# Kitchenkopf-v1.net
KiCad netlist of a schematic drawn in EAGLE
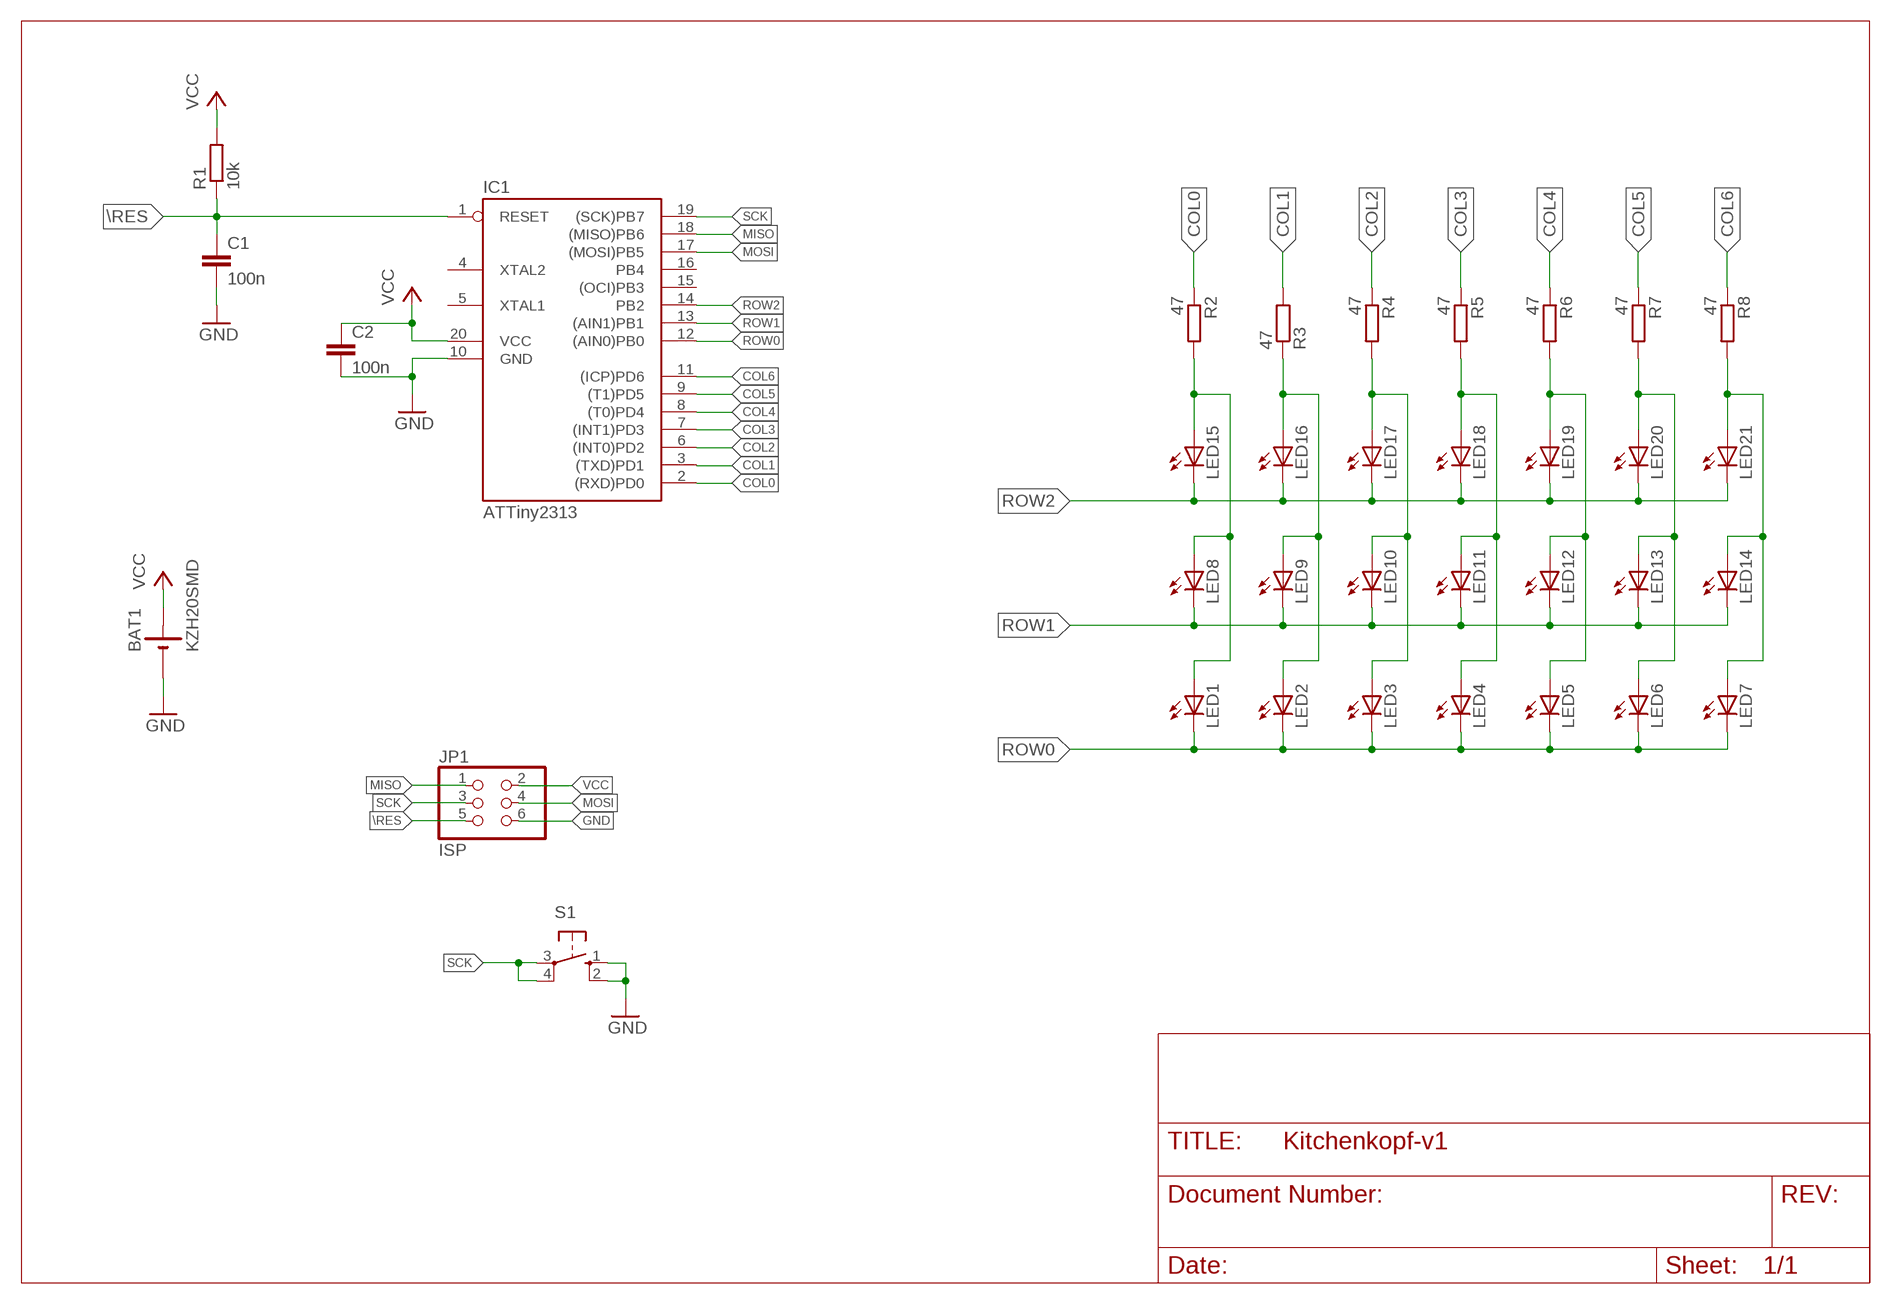
[diagram p0: schematic, sheet 1]

(export (version "E")
  (design (tool "Eeschema 10.0.6"))
  (components
    (comp (ref "BAT1")
      (value "KZH20SMD")
      (footprint "eagle-import:KZH20SMD")
      (libsource (lib "eagle-import") (part "KZH20SMD"))
    )
    (comp (ref "C1")
      (value "100n")
      (footprint "eagle-import:C0805")
      (libsource (lib "eagle-import") (part "C-EUC0805"))
    )
    (comp (ref "C2")
      (value "100n")
      (footprint "eagle-import:C0805")
      (libsource (lib "eagle-import") (part "C-EUC0805"))
    )
    (comp (ref "IC1")
      (value "ATTiny2313")
      (footprint "eagle-import:SO20L")
      (libsource (lib "eagle-import") (part "AT90S2313S"))
    )
    (comp (ref "JP1")
      (value "ISP")
      (footprint "eagle-import:2X03")
      (libsource (lib "eagle-import") (part "PINHD-2X3"))
    )
    (comp (ref "LED1")
      (value "LEDCHIP-LED0805")
      (footprint "eagle-import:CHIP-LED0805")
      (libsource (lib "eagle-import") (part "LEDCHIP-LED0805"))
    )
    (comp (ref "LED2")
      (value "LEDCHIP-LED0805")
      (footprint "eagle-import:CHIP-LED0805")
      (libsource (lib "eagle-import") (part "LEDCHIP-LED0805"))
    )
    (comp (ref "LED3")
      (value "LEDCHIP-LED0805")
      (footprint "eagle-import:CHIP-LED0805")
      (libsource (lib "eagle-import") (part "LEDCHIP-LED0805"))
    )
    (comp (ref "LED4")
      (value "LEDCHIP-LED0805")
      (footprint "eagle-import:CHIP-LED0805")
      (libsource (lib "eagle-import") (part "LEDCHIP-LED0805"))
    )
    (comp (ref "LED5")
      (value "LEDCHIP-LED0805")
      (footprint "eagle-import:CHIP-LED0805")
      (libsource (lib "eagle-import") (part "LEDCHIP-LED0805"))
    )
    (comp (ref "LED6")
      (value "LEDCHIP-LED0805")
      (footprint "eagle-import:CHIP-LED0805")
      (libsource (lib "eagle-import") (part "LEDCHIP-LED0805"))
    )
    (comp (ref "LED7")
      (value "LEDCHIP-LED0805")
      (footprint "eagle-import:CHIP-LED0805")
      (libsource (lib "eagle-import") (part "LEDCHIP-LED0805"))
    )
    (comp (ref "LED8")
      (value "LEDCHIP-LED0805")
      (footprint "eagle-import:CHIP-LED0805")
      (libsource (lib "eagle-import") (part "LEDCHIP-LED0805"))
    )
    (comp (ref "LED9")
      (value "LEDCHIP-LED0805")
      (footprint "eagle-import:CHIP-LED0805")
      (libsource (lib "eagle-import") (part "LEDCHIP-LED0805"))
    )
    (comp (ref "LED10")
      (value "LEDCHIP-LED0805")
      (footprint "eagle-import:CHIP-LED0805")
      (libsource (lib "eagle-import") (part "LEDCHIP-LED0805"))
    )
    (comp (ref "LED11")
      (value "LEDCHIP-LED0805")
      (footprint "eagle-import:CHIP-LED0805")
      (libsource (lib "eagle-import") (part "LEDCHIP-LED0805"))
    )
    (comp (ref "LED12")
      (value "LEDCHIP-LED0805")
      (footprint "eagle-import:CHIP-LED0805")
      (libsource (lib "eagle-import") (part "LEDCHIP-LED0805"))
    )
    (comp (ref "LED13")
      (value "LEDCHIP-LED0805")
      (footprint "eagle-import:CHIP-LED0805")
      (libsource (lib "eagle-import") (part "LEDCHIP-LED0805"))
    )
    (comp (ref "LED14")
      (value "LEDCHIP-LED0805")
      (footprint "eagle-import:CHIP-LED0805")
      (libsource (lib "eagle-import") (part "LEDCHIP-LED0805"))
    )
    (comp (ref "LED15")
      (value "LEDCHIP-LED0805")
      (footprint "eagle-import:CHIP-LED0805")
      (libsource (lib "eagle-import") (part "LEDCHIP-LED0805"))
    )
    (comp (ref "LED16")
      (value "LEDCHIP-LED0805")
      (footprint "eagle-import:CHIP-LED0805")
      (libsource (lib "eagle-import") (part "LEDCHIP-LED0805"))
    )
    (comp (ref "LED17")
      (value "LEDCHIP-LED0805")
      (footprint "eagle-import:CHIP-LED0805")
      (libsource (lib "eagle-import") (part "LEDCHIP-LED0805"))
    )
    (comp (ref "LED18")
      (value "LEDCHIP-LED0805")
      (footprint "eagle-import:CHIP-LED0805")
      (libsource (lib "eagle-import") (part "LEDCHIP-LED0805"))
    )
    (comp (ref "LED19")
      (value "LEDCHIP-LED0805")
      (footprint "eagle-import:CHIP-LED0805")
      (libsource (lib "eagle-import") (part "LEDCHIP-LED0805"))
    )
    (comp (ref "LED20")
      (value "LEDCHIP-LED0805")
      (footprint "eagle-import:CHIP-LED0805")
      (libsource (lib "eagle-import") (part "LEDCHIP-LED0805"))
    )
    (comp (ref "LED21")
      (value "LEDCHIP-LED0805")
      (footprint "eagle-import:CHIP-LED0805")
      (libsource (lib "eagle-import") (part "LEDCHIP-LED0805"))
    )
    (comp (ref "R1")
      (value "10k")
      (footprint "eagle-import:R0805")
      (libsource (lib "eagle-import") (part "R-EU_R0805"))
    )
    (comp (ref "R2")
      (value "47")
      (footprint "eagle-import:R0805")
      (libsource (lib "eagle-import") (part "R-EU_R0805"))
    )
    (comp (ref "R3")
      (value "47")
      (footprint "eagle-import:R0805")
      (libsource (lib "eagle-import") (part "R-EU_R0805"))
    )
    (comp (ref "R4")
      (value "47")
      (footprint "eagle-import:R0805")
      (libsource (lib "eagle-import") (part "R-EU_R0805"))
    )
    (comp (ref "R5")
      (value "47")
      (footprint "eagle-import:R0805")
      (libsource (lib "eagle-import") (part "R-EU_R0805"))
    )
    (comp (ref "R6")
      (value "47")
      (footprint "eagle-import:R0805")
      (libsource (lib "eagle-import") (part "R-EU_R0805"))
    )
    (comp (ref "R7")
      (value "47")
      (footprint "eagle-import:R0805")
      (libsource (lib "eagle-import") (part "R-EU_R0805"))
    )
    (comp (ref "R8")
      (value "47")
      (footprint "eagle-import:R0805")
      (libsource (lib "eagle-import") (part "R-EU_R0805"))
    )
    (comp (ref "S1")
      (value "10-XX")
      (footprint "eagle-import:B3F-10XX")
      (fields (field (name "MPN") "B3F-1000"))
      (libsource (lib "eagle-import") (part "10-XX"))
    )
  )
  (nets
    (net (code "1") (name "COL0") (class "Default")
      (node (ref "IC1") (pin "2") (pinfunction "(RXD)PD0_2") (pintype "bidirectional"))
      (node (ref "R2") (pin "1") (pinfunction "1_1") (pintype "passive"))
    )
    (net (code "2") (name "COL1") (class "Default")
      (node (ref "IC1") (pin "3") (pinfunction "(TXD)PD1_3") (pintype "bidirectional"))
      (node (ref "R3") (pin "2") (pinfunction "2_2") (pintype "passive"))
    )
    (net (code "3") (name "COL2") (class "Default")
      (node (ref "IC1") (pin "6") (pinfunction "(INT0)PD2_6") (pintype "bidirectional"))
      (node (ref "R4") (pin "1") (pinfunction "1_1") (pintype "passive"))
    )
    (net (code "4") (name "COL3") (class "Default")
      (node (ref "IC1") (pin "7") (pinfunction "(INT1)PD3_7") (pintype "bidirectional"))
      (node (ref "R5") (pin "1") (pinfunction "1_1") (pintype "passive"))
    )
    (net (code "5") (name "COL4") (class "Default")
      (node (ref "IC1") (pin "8") (pinfunction "(T0)PD4_8") (pintype "bidirectional"))
      (node (ref "R6") (pin "1") (pinfunction "1_1") (pintype "passive"))
    )
    (net (code "6") (name "COL5") (class "Default")
      (node (ref "IC1") (pin "9") (pinfunction "(T1)PD5_9") (pintype "bidirectional"))
      (node (ref "R7") (pin "1") (pinfunction "1_1") (pintype "passive"))
    )
    (net (code "7") (name "COL6") (class "Default")
      (node (ref "IC1") (pin "11") (pinfunction "(ICP)PD6_11") (pintype "bidirectional"))
      (node (ref "R8") (pin "1") (pinfunction "1_1") (pintype "passive"))
    )
    (net (code "8") (name "GND") (class "Default")
      (node (ref "BAT1") (pin "NEG") (pinfunction "-_NEG") (pintype "power_in"))
      (node (ref "C1") (pin "2") (pinfunction "2_2") (pintype "passive"))
      (node (ref "C2") (pin "2") (pinfunction "2_2") (pintype "passive"))
      (node (ref "IC1") (pin "10") (pinfunction "GND_10") (pintype "power_in"))
      (node (ref "JP1") (pin "6") (pinfunction "6_6") (pintype "passive"))
      (node (ref "S1") (pin "1") (pinfunction "S_1") (pintype "passive"))
      (node (ref "S1") (pin "2") (pinfunction "S1_2") (pintype "passive"))
    )
    (net (code "9") (name "MISO") (class "Default")
      (node (ref "IC1") (pin "18") (pinfunction "(MISO)PB6_18") (pintype "bidirectional"))
      (node (ref "JP1") (pin "1") (pinfunction "1_1") (pintype "passive"))
    )
    (net (code "10") (name "MOSI") (class "Default")
      (node (ref "IC1") (pin "17") (pinfunction "(MOSI)PB5_17") (pintype "bidirectional"))
      (node (ref "JP1") (pin "4") (pinfunction "4_4") (pintype "passive"))
    )
    (net (code "11") (name "Net-(LED1-PadA)") (class "Default")
      (node (ref "LED1") (pin "A") (pinfunction "A_A") (pintype "passive"))
      (node (ref "LED15") (pin "A") (pinfunction "A_A") (pintype "passive"))
      (node (ref "LED8") (pin "A") (pinfunction "A_A") (pintype "passive"))
      (node (ref "R2") (pin "2") (pinfunction "2_2") (pintype "passive"))
    )
    (net (code "12") (name "Net-(LED10-PadA)") (class "Default")
      (node (ref "LED10") (pin "A") (pinfunction "A_A") (pintype "passive"))
      (node (ref "LED17") (pin "A") (pinfunction "A_A") (pintype "passive"))
      (node (ref "LED3") (pin "A") (pinfunction "A_A") (pintype "passive"))
      (node (ref "R4") (pin "2") (pinfunction "2_2") (pintype "passive"))
    )
    (net (code "13") (name "Net-(LED11-PadA)") (class "Default")
      (node (ref "LED11") (pin "A") (pinfunction "A_A") (pintype "passive"))
      (node (ref "LED18") (pin "A") (pinfunction "A_A") (pintype "passive"))
      (node (ref "LED4") (pin "A") (pinfunction "A_A") (pintype "passive"))
      (node (ref "R5") (pin "2") (pinfunction "2_2") (pintype "passive"))
    )
    (net (code "14") (name "Net-(LED12-PadA)") (class "Default")
      (node (ref "LED12") (pin "A") (pinfunction "A_A") (pintype "passive"))
      (node (ref "LED19") (pin "A") (pinfunction "A_A") (pintype "passive"))
      (node (ref "LED5") (pin "A") (pinfunction "A_A") (pintype "passive"))
      (node (ref "R6") (pin "2") (pinfunction "2_2") (pintype "passive"))
    )
    (net (code "15") (name "Net-(LED13-PadA)") (class "Default")
      (node (ref "LED13") (pin "A") (pinfunction "A_A") (pintype "passive"))
      (node (ref "LED20") (pin "A") (pinfunction "A_A") (pintype "passive"))
      (node (ref "LED6") (pin "A") (pinfunction "A_A") (pintype "passive"))
      (node (ref "R7") (pin "2") (pinfunction "2_2") (pintype "passive"))
    )
    (net (code "16") (name "Net-(LED14-PadA)") (class "Default")
      (node (ref "LED14") (pin "A") (pinfunction "A_A") (pintype "passive"))
      (node (ref "LED21") (pin "A") (pinfunction "A_A") (pintype "passive"))
      (node (ref "LED7") (pin "A") (pinfunction "A_A") (pintype "passive"))
      (node (ref "R8") (pin "2") (pinfunction "2_2") (pintype "passive"))
    )
    (net (code "17") (name "Net-(LED16-PadA)") (class "Default")
      (node (ref "LED16") (pin "A") (pinfunction "A_A") (pintype "passive"))
      (node (ref "LED2") (pin "A") (pinfunction "A_A") (pintype "passive"))
      (node (ref "LED9") (pin "A") (pinfunction "A_A") (pintype "passive"))
      (node (ref "R3") (pin "1") (pinfunction "1_1") (pintype "passive"))
    )
    (net (code "18") (name "ROW0") (class "Default")
      (node (ref "IC1") (pin "12") (pinfunction "(AIN0)PB0_12") (pintype "bidirectional"))
      (node (ref "LED1") (pin "C") (pinfunction "C_C") (pintype "passive"))
      (node (ref "LED2") (pin "C") (pinfunction "C_C") (pintype "passive"))
      (node (ref "LED3") (pin "C") (pinfunction "C_C") (pintype "passive"))
      (node (ref "LED4") (pin "C") (pinfunction "C_C") (pintype "passive"))
      (node (ref "LED5") (pin "C") (pinfunction "C_C") (pintype "passive"))
      (node (ref "LED6") (pin "C") (pinfunction "C_C") (pintype "passive"))
      (node (ref "LED7") (pin "C") (pinfunction "C_C") (pintype "passive"))
    )
    (net (code "19") (name "ROW1") (class "Default")
      (node (ref "IC1") (pin "13") (pinfunction "(AIN1)PB1_13") (pintype "bidirectional"))
      (node (ref "LED10") (pin "C") (pinfunction "C_C") (pintype "passive"))
      (node (ref "LED11") (pin "C") (pinfunction "C_C") (pintype "passive"))
      (node (ref "LED12") (pin "C") (pinfunction "C_C") (pintype "passive"))
      (node (ref "LED13") (pin "C") (pinfunction "C_C") (pintype "passive"))
      (node (ref "LED14") (pin "C") (pinfunction "C_C") (pintype "passive"))
      (node (ref "LED8") (pin "C") (pinfunction "C_C") (pintype "passive"))
      (node (ref "LED9") (pin "C") (pinfunction "C_C") (pintype "passive"))
    )
    (net (code "20") (name "ROW2") (class "Default")
      (node (ref "IC1") (pin "14") (pinfunction "PB2_14") (pintype "bidirectional"))
      (node (ref "LED15") (pin "C") (pinfunction "C_C") (pintype "passive"))
      (node (ref "LED16") (pin "C") (pinfunction "C_C") (pintype "passive"))
      (node (ref "LED17") (pin "C") (pinfunction "C_C") (pintype "passive"))
      (node (ref "LED18") (pin "C") (pinfunction "C_C") (pintype "passive"))
      (node (ref "LED19") (pin "C") (pinfunction "C_C") (pintype "passive"))
      (node (ref "LED20") (pin "C") (pinfunction "C_C") (pintype "passive"))
      (node (ref "LED21") (pin "C") (pinfunction "C_C") (pintype "passive"))
    )
    (net (code "21") (name "SCK") (class "Default")
      (node (ref "IC1") (pin "19") (pinfunction "(SCK)PB7_19") (pintype "bidirectional"))
      (node (ref "JP1") (pin "3") (pinfunction "3_3") (pintype "passive"))
      (node (ref "S1") (pin "3") (pinfunction "P_3") (pintype "passive"))
      (node (ref "S1") (pin "4") (pinfunction "P1_4") (pintype "passive"))
    )
    (net (code "22") (name "VCC") (class "Default")
      (node (ref "BAT1") (pin "POS") (pinfunction "+_POS") (pintype "power_in"))
      (node (ref "C2") (pin "1") (pinfunction "1_1") (pintype "passive"))
      (node (ref "IC1") (pin "20") (pinfunction "VCC_20") (pintype "power_in"))
      (node (ref "JP1") (pin "2") (pinfunction "2_2") (pintype "passive"))
      (node (ref "R1") (pin "2") (pinfunction "2_2") (pintype "passive"))
    )
    (net (code "23") (name "\\RES") (class "Default")
      (node (ref "C1") (pin "1") (pinfunction "1_1") (pintype "passive"))
      (node (ref "IC1") (pin "1") (pinfunction "RESET_1") (pintype "bidirectional"))
      (node (ref "JP1") (pin "5") (pinfunction "5_5") (pintype "passive"))
      (node (ref "R1") (pin "1") (pinfunction "1_1") (pintype "passive"))
    )
    (net (code "24") (name "unconnected-(IC1-(OCI)PB3-Pad15)") (class "Default")
      (node (ref "IC1") (pin "15") (pinfunction "(OCI)PB3_15") (pintype "bidirectional"))
    )
    (net (code "25") (name "unconnected-(IC1-PB4-Pad16)") (class "Default")
      (node (ref "IC1") (pin "16") (pinfunction "PB4_16") (pintype "bidirectional"))
    )
    (net (code "26") (name "unconnected-(IC1-XTAL1-Pad5)") (class "Default")
      (node (ref "IC1") (pin "5") (pinfunction "XTAL1_5") (pintype "bidirectional"))
    )
    (net (code "27") (name "unconnected-(IC1-XTAL2-Pad4)") (class "Default")
      (node (ref "IC1") (pin "4") (pinfunction "XTAL2_4") (pintype "bidirectional"))
    )
  )
)
